# interface.net
KiCad netlist of a schematic drawn in Altium Designer
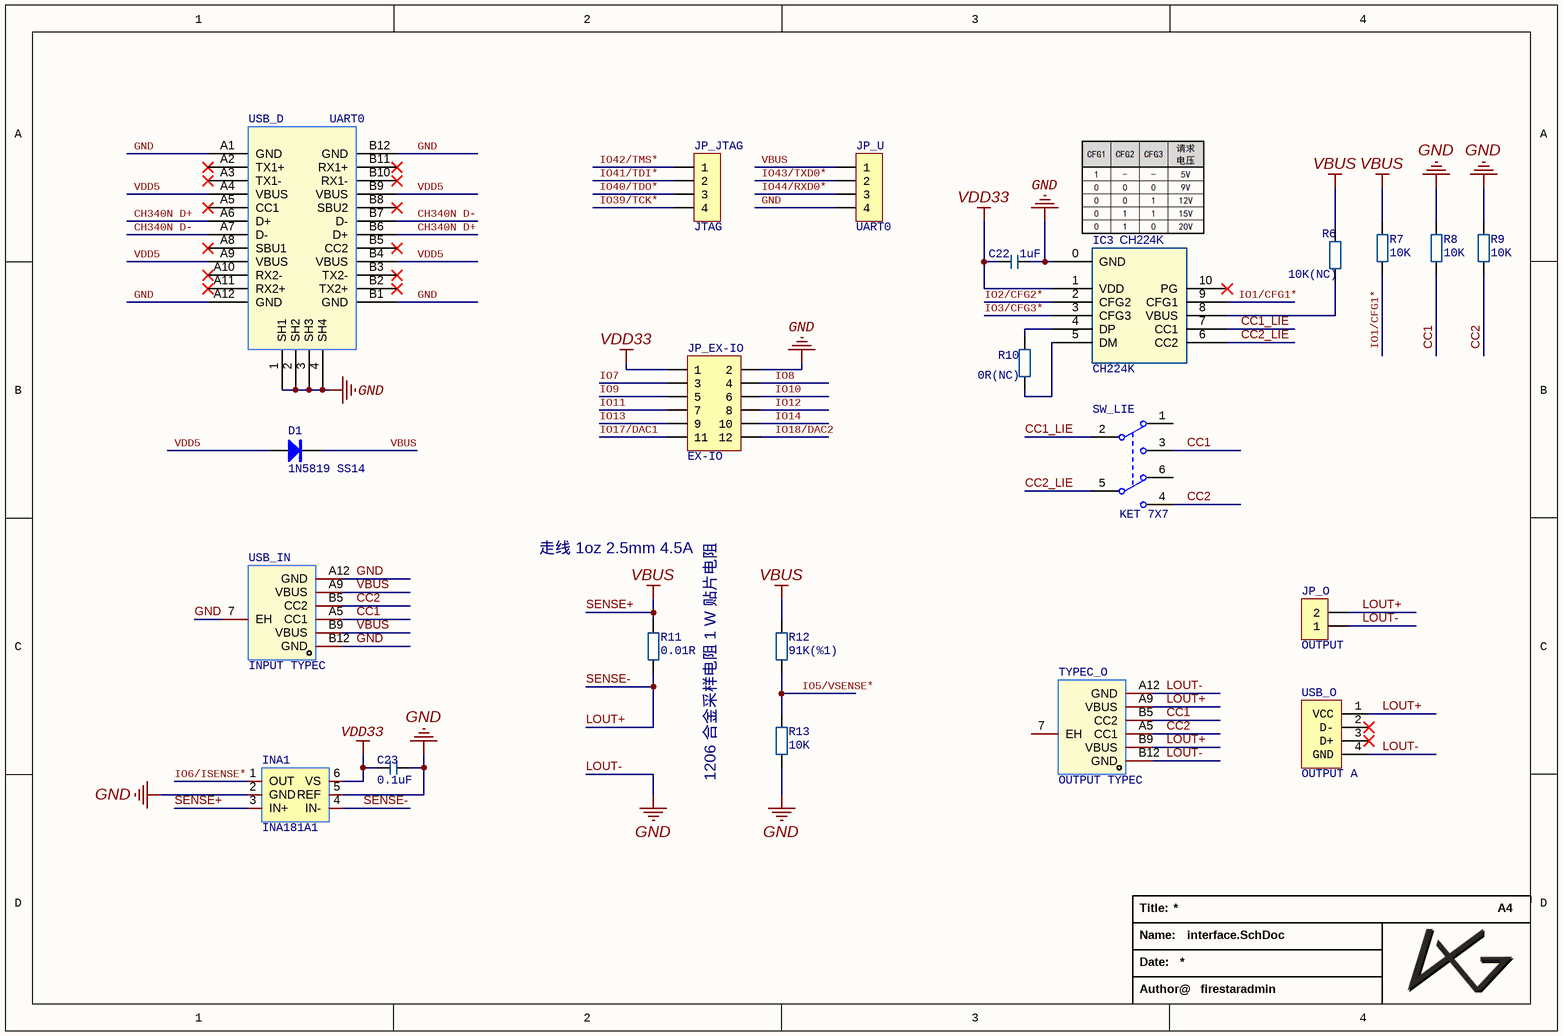
[diagram p0: interface.SchDoc]

(export (version "E")
  (design (tool "Eeschema 10.0.6"))
  (components
    (comp (ref "C22")
      (value "1uF")
      (footprint "C 0603_L")
      (description "无极性贴片电容")
      (fields (field (name "版权归属") "源创客"))
      (libsource (lib "SCH-电阻-电容-电感") (part "C"))
    )
    (comp (ref "C23")
      (value "0.1uF")
      (footprint "C 0603_L")
      (description "无极性贴片电容")
      (fields (field (name "版权归属") "源创客"))
      (libsource (lib "SCH-电阻-电容-电感") (part "C"))
    )
    (comp (ref "D1")
      (value "1N5819 SS14")
      (footprint "SOD-323")
      (description "肖特基二极管")
      (fields (field (name "版权归属") "源创客"))
      (libsource (lib "SCH-二极管-整流桥") (part "1N5819"))
    )
    (comp (ref "IC3")
      (value "CH224K")
      (footprint "ESSOP10-1mm")
      (libsource (lib "SCH-电源类芯片") (part "CH224K"))
    )
    (comp (ref "INA1")
      (value "INA181A1")
      (footprint "SOT23-6L")
      (description "电流检测")
      (libsource (lib "SCH-IC芯片") (part "INA181A1"))
    )
    (comp (ref "JP_EX-IO")
      (value "EX-IO")
      (footprint "HDR2.54-LI-2x6P")
      (description "6*2P接插件")
      (fields (field (name "版权归属") "源创客"))
      (libsource (lib "SCH-接插件-2.54mm") (part "Header  6X2"))
    )
    (comp (ref "JP_JTAG")
      (value "JTAG")
      (footprint "HDR2.54-LI-4P")
      (description "4P接插件")
      (fields (field (name "版权归属") "源创客"))
      (libsource (lib "SCH-接插件-2.54mm") (part "Header 4"))
    )
    (comp (ref "JP_O")
      (value "OUTPUT")
      (footprint "KF301-5.0-2P")
      (description "2P接插件")
      (fields (field (name "版权归属") "源创客"))
      (libsource (lib "SCH-接插件-5.0mm") (part "Header 2"))
    )
    (comp (ref "JP_U")
      (value "UART0")
      (footprint "HDR2.54-LI-4P")
      (description "4P接插件")
      (fields (field (name "版权归属") "源创客"))
      (libsource (lib "SCH-接插件-2.54mm") (part "Header 4"))
    )
    (comp (ref "R6")
      (value "10K(NC)")
      (footprint "R 0603_L")
      (description "贴片电阻")
      (fields (field (name "版权归属") "源创客"))
      (libsource (lib "SCH-电阻-电容-电感") (part "R"))
    )
    (comp (ref "R7")
      (value "10K")
      (footprint "R 0603_L")
      (description "贴片电阻")
      (fields (field (name "版权归属") "源创客"))
      (libsource (lib "SCH-电阻-电容-电感") (part "R"))
    )
    (comp (ref "R8")
      (value "10K")
      (footprint "R 0603_L")
      (description "贴片电阻")
      (fields (field (name "版权归属") "源创客"))
      (libsource (lib "SCH-电阻-电容-电感") (part "R"))
    )
    (comp (ref "R9")
      (value "10K")
      (footprint "R 0603_L")
      (description "贴片电阻")
      (fields (field (name "版权归属") "源创客"))
      (libsource (lib "SCH-电阻-电容-电感") (part "R"))
    )
    (comp (ref "R10")
      (value "0R(NC)")
      (footprint "R 0603_L")
      (description "贴片电阻")
      (fields (field (name "版权归属") "源创客"))
      (libsource (lib "SCH-电阻-电容-电感") (part "R"))
    )
    (comp (ref "R11")
      (value "0.01R")
      (footprint "R 1206_L")
      (description "1206 合金采样电阻 1 W 贴片电阻")
      (fields (field (name "版权归属") "源创客"))
      (libsource (lib "SCH-电阻-电容-电感") (part "R"))
    )
    (comp (ref "R12")
      (value "91K(%1)")
      (footprint "R 0603_L")
      (description "贴片电阻")
      (fields (field (name "版权归属") "源创客"))
      (libsource (lib "SCH-电阻-电容-电感") (part "R"))
    )
    (comp (ref "R13")
      (value "10K")
      (footprint "R 0603_L")
      (description "贴片电阻")
      (fields (field (name "版权归属") "源创客"))
      (libsource (lib "SCH-电阻-电容-电感") (part "R"))
    )
    (comp (ref "SW_LIE")
      (value "KET 7X7")
      (footprint "KFT DIP-7X7")
      (description "7*7自锁开关")
      (fields (field (name "版权归属") "源创客"))
      (libsource (lib "SCH-按键-开关") (part "KET 7X7"))
    )
    (comp (ref "TYPEC_O")
      (value "OUTPUT TYPEC")
      (footprint "TYPE-C-6P")
      (fields (field (name "MANUFACTURER") "SHOU HAN(首韩)") (field (name "MANUFACTURER PART") "TYPE-C 6P"))
      (libsource (lib "SCH-接口类") (part "TYPE-C 6P"))
    )
    (comp (ref "USB_D")
      (value "UART0")
      (footprint "TYPE-C-16P")
      (description "Type-C 16Pin")
      (libsource (lib "SCH-接口类") (part "TypeC-16P"))
    )
    (comp (ref "USB_IN")
      (value "INPUT TYPEC")
      (footprint "TYPE-C-6P")
      (fields (field (name "MANUFACTURER") "SHOU HAN(首韩)") (field (name "MANUFACTURER PART") "TYPE-C 6P"))
      (libsource (lib "SCH-接口类") (part "TYPE-C 6P"))
    )
    (comp (ref "USB_O")
      (value "OUTPUT A")
      (footprint "USB-A/S_B")
      (description "USB-A型母接口")
      (fields (field (name "版权归属") "源创客"))
      (libsource (lib "SCH-接口类") (part "USB-A/S"))
    )
  )
  (nets
    (net (code "1") (name "/CC1") (class "Default")
      (node (ref "R8") (pin "2") (pinfunction "2_2") (pintype "passive"))
      (node (ref "SW_LIE") (pin "3") (pinfunction "NO1_3") (pintype "passive"))
      (node (ref "TYPEC_O") (pin "B5") (pinfunction "CC2_B5") (pintype "passive"))
      (node (ref "USB_IN") (pin "A5") (pinfunction "CC1_A5") (pintype "passive"))
    )
    (net (code "2") (name "/CC1_LIE") (class "Default")
      (node (ref "IC3") (pin "7") (pinfunction "CC1_7") (pintype "passive"))
      (node (ref "SW_LIE") (pin "2") (pinfunction "COM2_2") (pintype "passive"))
    )
    (net (code "3") (name "/CC2") (class "Default")
      (node (ref "R9") (pin "2") (pinfunction "2_2") (pintype "passive"))
      (node (ref "SW_LIE") (pin "4") (pinfunction "NO2_4") (pintype "passive"))
      (node (ref "TYPEC_O") (pin "A5") (pinfunction "CC1_A5") (pintype "passive"))
      (node (ref "USB_IN") (pin "B5") (pinfunction "CC2_B5") (pintype "passive"))
    )
    (net (code "4") (name "/CC2_LIE") (class "Default")
      (node (ref "IC3") (pin "6") (pinfunction "CC2_6") (pintype "passive"))
      (node (ref "SW_LIE") (pin "5") (pinfunction "COM2_5") (pintype "passive"))
    )
    (net (code "5") (name "/CH340N D+") (class "Default")
      (node (ref "USB_D") (pin "A6") (pinfunction "D+_A6") (pintype "passive"))
      (node (ref "USB_D") (pin "B6") (pinfunction "D+_B6") (pintype "passive"))
    )
    (net (code "6") (name "/CH340N D-") (class "Default")
      (node (ref "USB_D") (pin "A7") (pinfunction "D-_A7") (pintype "passive"))
      (node (ref "USB_D") (pin "B7") (pinfunction "D-_B7") (pintype "passive"))
    )
    (net (code "7") (name "/IO1{slash}CFG1*") (class "Default")
      (node (ref "IC3") (pin "9") (pinfunction "CFG1_9") (pintype "passive"))
      (node (ref "R7") (pin "2") (pinfunction "2_2") (pintype "passive"))
    )
    (net (code "8") (name "/IO2{slash}CFG2*") (class "Default")
      (node (ref "IC3") (pin "2") (pinfunction "CFG2_2") (pintype "passive"))
    )
    (net (code "9") (name "/IO3{slash}CFG3*") (class "Default")
      (node (ref "IC3") (pin "3") (pinfunction "CFG3_3") (pintype "passive"))
    )
    (net (code "10") (name "/IO5{slash}VSENSE*") (class "Default")
      (node (ref "R12") (pin "1") (pinfunction "1_1") (pintype "passive"))
      (node (ref "R13") (pin "2") (pinfunction "2_2") (pintype "passive"))
    )
    (net (code "11") (name "/IO6{slash}ISENSE*") (class "Default")
      (node (ref "INA1") (pin "1") (pinfunction "OUT_1") (pintype "passive"))
    )
    (net (code "12") (name "/IO7") (class "Default")
      (node (ref "JP_EX-IO") (pin "3") (pinfunction "3_3") (pintype "passive"))
    )
    (net (code "13") (name "/IO8") (class "Default")
      (node (ref "JP_EX-IO") (pin "4") (pinfunction "4_4") (pintype "passive"))
    )
    (net (code "14") (name "/IO9") (class "Default")
      (node (ref "JP_EX-IO") (pin "5") (pinfunction "5_5") (pintype "passive"))
    )
    (net (code "15") (name "/IO10") (class "Default")
      (node (ref "JP_EX-IO") (pin "6") (pinfunction "6_6") (pintype "passive"))
    )
    (net (code "16") (name "/IO11") (class "Default")
      (node (ref "JP_EX-IO") (pin "7") (pinfunction "7_7") (pintype "passive"))
    )
    (net (code "17") (name "/IO12") (class "Default")
      (node (ref "JP_EX-IO") (pin "8") (pinfunction "8_8") (pintype "passive"))
    )
    (net (code "18") (name "/IO13") (class "Default")
      (node (ref "JP_EX-IO") (pin "9") (pinfunction "9_9") (pintype "passive"))
    )
    (net (code "19") (name "/IO14") (class "Default")
      (node (ref "JP_EX-IO") (pin "10") (pinfunction "10_10") (pintype "passive"))
    )
    (net (code "20") (name "/IO17{slash}DAC1") (class "Default")
      (node (ref "JP_EX-IO") (pin "11") (pinfunction "11_11") (pintype "passive"))
    )
    (net (code "21") (name "/IO18{slash}DAC2") (class "Default")
      (node (ref "JP_EX-IO") (pin "12") (pinfunction "12_12") (pintype "passive"))
    )
    (net (code "22") (name "/IO39{slash}TCK*") (class "Default")
      (node (ref "JP_JTAG") (pin "4") (pinfunction "4_4") (pintype "passive"))
    )
    (net (code "23") (name "/IO40{slash}TDO*") (class "Default")
      (node (ref "JP_JTAG") (pin "3") (pinfunction "3_3") (pintype "passive"))
    )
    (net (code "24") (name "/IO41{slash}TDI*") (class "Default")
      (node (ref "JP_JTAG") (pin "2") (pinfunction "2_2") (pintype "passive"))
    )
    (net (code "25") (name "/IO42{slash}TMS*") (class "Default")
      (node (ref "JP_JTAG") (pin "1") (pinfunction "1_1") (pintype "passive"))
    )
    (net (code "26") (name "/IO43{slash}TXD0*") (class "Default")
      (node (ref "JP_U") (pin "2") (pinfunction "2_2") (pintype "passive"))
    )
    (net (code "27") (name "/IO44{slash}RXD0*") (class "Default")
      (node (ref "JP_U") (pin "3") (pinfunction "3_3") (pintype "passive"))
    )
    (net (code "28") (name "/LOUT+") (class "Default")
      (node (ref "INA1") (pin "4") (pinfunction "IN-_4") (pintype "passive"))
      (node (ref "JP_O") (pin "2") (pinfunction "2_2") (pintype "passive"))
      (node (ref "R11") (pin "1") (pinfunction "1_1") (pintype "passive"))
      (node (ref "TYPEC_O") (pin "A9") (pinfunction "VBUS_A9") (pintype "passive"))
      (node (ref "TYPEC_O") (pin "B9") (pinfunction "VBUS_B9") (pintype "passive"))
      (node (ref "USB_O") (pin "1") (pinfunction "VCC_1") (pintype "passive"))
    )
    (net (code "29") (name "/VDD5") (class "Default")
      (node (ref "D1") (pin "1") (pinfunction "A_1") (pintype "passive"))
      (node (ref "USB_D") (pin "A4") (pinfunction "VBUS_A4") (pintype "passive"))
      (node (ref "USB_D") (pin "A9") (pinfunction "VBUS_A9") (pintype "passive"))
      (node (ref "USB_D") (pin "B4") (pinfunction "VBUS_B4") (pintype "passive"))
      (node (ref "USB_D") (pin "B9") (pinfunction "VBUS_B9") (pintype "passive"))
    )
    (net (code "30") (name "GND") (class "Default")
      (node (ref "C22") (pin "1") (pinfunction "1_1") (pintype "passive"))
      (node (ref "C23") (pin "1") (pinfunction "1_1") (pintype "passive"))
      (node (ref "IC3") (pin "0") (pinfunction "GND_0") (pintype "passive"))
      (node (ref "INA1") (pin "2") (pinfunction "GND_2") (pintype "passive"))
      (node (ref "INA1") (pin "5") (pinfunction "REF_5") (pintype "passive"))
      (node (ref "JP_EX-IO") (pin "2") (pinfunction "2_2") (pintype "passive"))
      (node (ref "JP_O") (pin "1") (pinfunction "1_1") (pintype "passive"))
      (node (ref "JP_U") (pin "4") (pinfunction "4_4") (pintype "passive"))
      (node (ref "R13") (pin "1") (pinfunction "1_1") (pintype "passive"))
      (node (ref "R8") (pin "1") (pinfunction "1_1") (pintype "passive"))
      (node (ref "R9") (pin "1") (pinfunction "1_1") (pintype "passive"))
      (node (ref "TYPEC_O") (pin "A12") (pinfunction "GND_A12") (pintype "passive"))
      (node (ref "TYPEC_O") (pin "B12") (pinfunction "GND_B12") (pintype "passive"))
      (node (ref "USB_D") (pin "1") (pinfunction "SH1_1") (pintype "passive"))
      (node (ref "USB_D") (pin "2") (pinfunction "SH2_2") (pintype "passive"))
      (node (ref "USB_D") (pin "3") (pinfunction "SH3_3") (pintype "passive"))
      (node (ref "USB_D") (pin "4") (pinfunction "SH4_4") (pintype "passive"))
      (node (ref "USB_D") (pin "A1") (pinfunction "GND_A1") (pintype "passive"))
      (node (ref "USB_D") (pin "A12") (pinfunction "GND_A12") (pintype "passive"))
      (node (ref "USB_D") (pin "B1") (pinfunction "GND_B1") (pintype "passive"))
      (node (ref "USB_D") (pin "B12") (pinfunction "GND_B12") (pintype "passive"))
      (node (ref "USB_IN") (pin "7") (pinfunction "EH_7") (pintype "passive"))
      (node (ref "USB_IN") (pin "A12") (pinfunction "GND_A12") (pintype "passive"))
      (node (ref "USB_IN") (pin "B12") (pinfunction "GND_B12") (pintype "passive"))
      (node (ref "USB_O") (pin "4") (pinfunction "GND_4") (pintype "passive"))
    )
    (net (code "31") (name "Net-(IC3-DM)") (class "Default")
      (node (ref "IC3") (pin "5") (pinfunction "DM_5") (pintype "passive"))
      (node (ref "R10") (pin "2") (pinfunction "2_2") (pintype "passive"))
    )
    (net (code "32") (name "Net-(IC3-DP)") (class "Default")
      (node (ref "IC3") (pin "4") (pinfunction "DP_4") (pintype "passive"))
      (node (ref "R10") (pin "1") (pinfunction "1_1") (pintype "passive"))
    )
    (net (code "33") (name "Net-(IC3-VBUS)") (class "Default")
      (node (ref "IC3") (pin "8") (pinfunction "VBUS_8") (pintype "passive"))
      (node (ref "R6") (pin "2") (pinfunction "2_2") (pintype "passive"))
    )
    (net (code "34") (name "VBUS") (class "Default")
      (node (ref "D1") (pin "2") (pinfunction "K_2") (pintype "passive"))
      (node (ref "INA1") (pin "3") (pinfunction "IN+_3") (pintype "passive"))
      (node (ref "JP_U") (pin "1") (pinfunction "1_1") (pintype "passive"))
      (node (ref "R11") (pin "2") (pinfunction "2_2") (pintype "passive"))
      (node (ref "R12") (pin "2") (pinfunction "2_2") (pintype "passive"))
      (node (ref "R6") (pin "1") (pinfunction "1_1") (pintype "passive"))
      (node (ref "R7") (pin "1") (pinfunction "1_1") (pintype "passive"))
      (node (ref "USB_IN") (pin "A9") (pinfunction "VBUS_A9") (pintype "passive"))
      (node (ref "USB_IN") (pin "B9") (pinfunction "VBUS_B9") (pintype "passive"))
    )
    (net (code "35") (name "VDD33") (class "Default")
      (node (ref "C22") (pin "2") (pinfunction "2_2") (pintype "passive"))
      (node (ref "C23") (pin "2") (pinfunction "2_2") (pintype "passive"))
      (node (ref "IC3") (pin "1") (pinfunction "VDD_1") (pintype "passive"))
      (node (ref "INA1") (pin "6") (pinfunction "VS_6") (pintype "passive"))
      (node (ref "JP_EX-IO") (pin "1") (pinfunction "1_1") (pintype "passive"))
    )
    (net (code "36") (name "unconnected-(IC3-PG-Pad10)") (class "Default")
      (node (ref "IC3") (pin "10") (pinfunction "PG_10") (pintype "passive+no_connect"))
    )
    (net (code "37") (name "unconnected-(SW_LIE-NC1-Pad1)") (class "Default")
      (node (ref "SW_LIE") (pin "1") (pinfunction "NC1_1") (pintype "passive"))
    )
    (net (code "38") (name "unconnected-(SW_LIE-NC2-Pad6)") (class "Default")
      (node (ref "SW_LIE") (pin "6") (pinfunction "NC2_6") (pintype "passive"))
    )
    (net (code "39") (name "unconnected-(TYPEC_O-EH-Pad7)") (class "Default")
      (node (ref "TYPEC_O") (pin "7") (pinfunction "EH_7") (pintype "passive"))
    )
    (net (code "40") (name "unconnected-(USB_D-CC1-PadA5)") (class "Default")
      (node (ref "USB_D") (pin "A5") (pinfunction "CC1_A5") (pintype "passive+no_connect"))
    )
    (net (code "41") (name "unconnected-(USB_D-CC2-PadB5)") (class "Default")
      (node (ref "USB_D") (pin "B5") (pinfunction "CC2_B5") (pintype "passive+no_connect"))
    )
    (net (code "42") (name "unconnected-(USB_D-RX1+-PadB11)") (class "Default")
      (node (ref "USB_D") (pin "B11") (pinfunction "RX1+_B11") (pintype "passive+no_connect"))
    )
    (net (code "43") (name "unconnected-(USB_D-RX1--PadB10)") (class "Default")
      (node (ref "USB_D") (pin "B10") (pinfunction "RX1-_B10") (pintype "passive+no_connect"))
    )
    (net (code "44") (name "unconnected-(USB_D-RX2+-PadA11)") (class "Default")
      (node (ref "USB_D") (pin "A11") (pinfunction "RX2+_A11") (pintype "passive+no_connect"))
    )
    (net (code "45") (name "unconnected-(USB_D-RX2--PadA10)") (class "Default")
      (node (ref "USB_D") (pin "A10") (pinfunction "RX2-_A10") (pintype "passive+no_connect"))
    )
    (net (code "46") (name "unconnected-(USB_D-SBU1-PadA8)") (class "Default")
      (node (ref "USB_D") (pin "A8") (pinfunction "SBU1_A8") (pintype "passive+no_connect"))
    )
    (net (code "47") (name "unconnected-(USB_D-SBU2-PadB8)") (class "Default")
      (node (ref "USB_D") (pin "B8") (pinfunction "SBU2_B8") (pintype "passive+no_connect"))
    )
    (net (code "48") (name "unconnected-(USB_D-TX1+-PadA2)") (class "Default")
      (node (ref "USB_D") (pin "A2") (pinfunction "TX1+_A2") (pintype "passive+no_connect"))
    )
    (net (code "49") (name "unconnected-(USB_D-TX1--PadA3)") (class "Default")
      (node (ref "USB_D") (pin "A3") (pinfunction "TX1-_A3") (pintype "passive+no_connect"))
    )
    (net (code "50") (name "unconnected-(USB_D-TX2+-PadB2)") (class "Default")
      (node (ref "USB_D") (pin "B2") (pinfunction "TX2+_B2") (pintype "passive+no_connect"))
    )
    (net (code "51") (name "unconnected-(USB_D-TX2--PadB3)") (class "Default")
      (node (ref "USB_D") (pin "B3") (pinfunction "TX2-_B3") (pintype "passive+no_connect"))
    )
    (net (code "52") (name "unconnected-(USB_O-D+-Pad3)") (class "Default")
      (node (ref "USB_O") (pin "3") (pinfunction "D+_3") (pintype "passive+no_connect"))
    )
    (net (code "53") (name "unconnected-(USB_O-D--Pad2)") (class "Default")
      (node (ref "USB_O") (pin "2") (pinfunction "D-_2") (pintype "passive+no_connect"))
    )
  )
)
